# ArduinoMega.net
KiCad netlist of a schematic drawn in Altium Designer
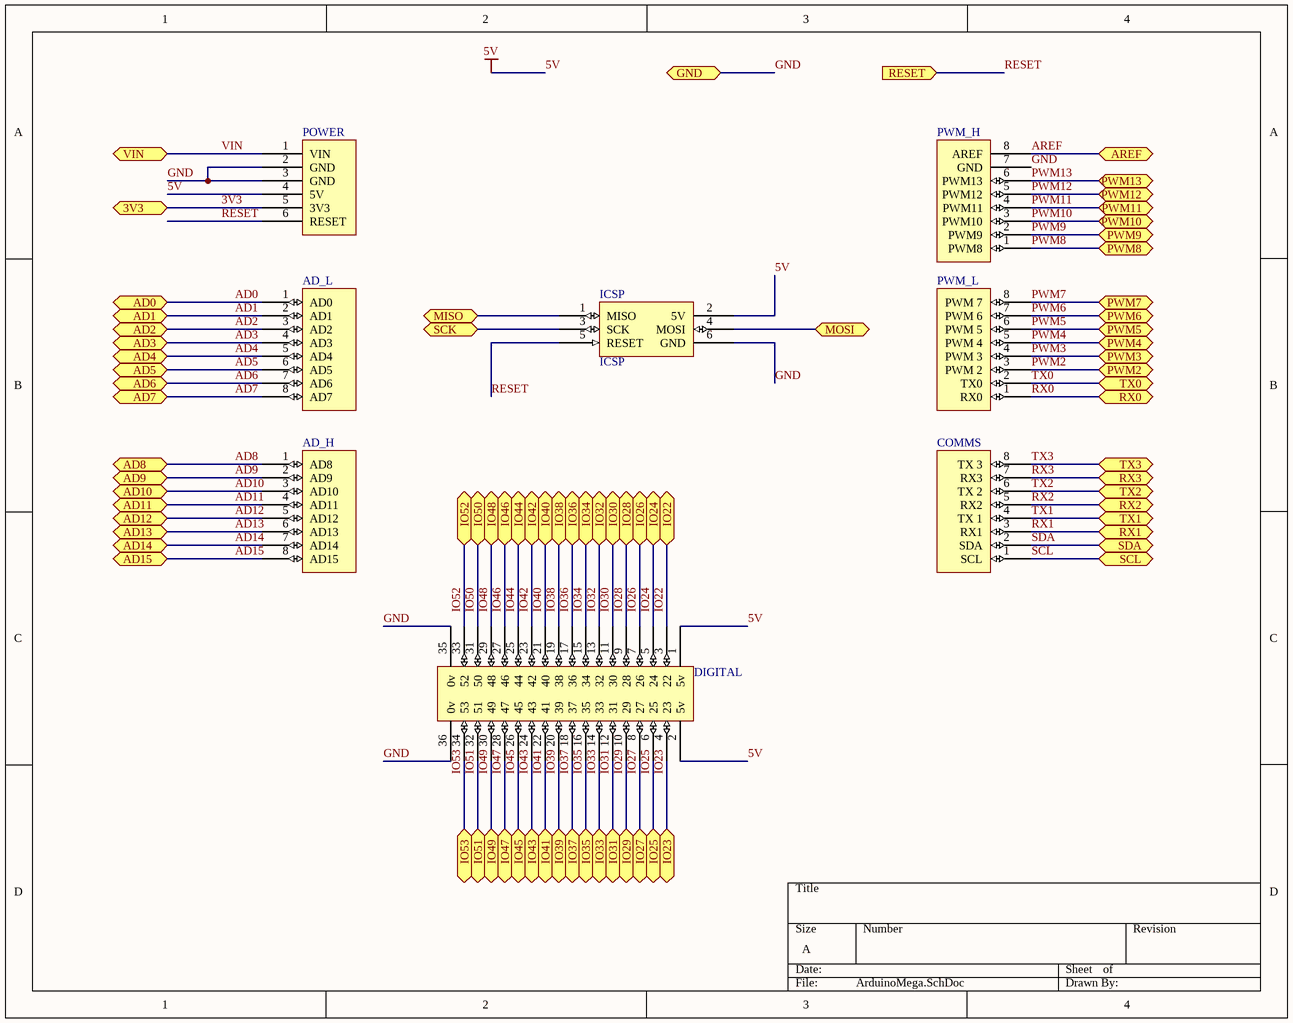
[diagram p0: ArduinoMega.SchDoc]

(export (version "E")
  (design (tool "Eeschema 10.0.6"))
  (components
    (comp (ref "AD_H") (value "AD_H") (footprint "HDR1X8") (libsource (lib "Header") (part "AD_H")))
    (comp (ref "AD_L") (value "AD_L") (footprint "HDR1X8") (libsource (lib "Header") (part "AD_L")))
    (comp (ref "COMMS")
      (value "Communication")
      (footprint "HDR1X8")
      (libsource (lib "Header") (part "Communication"))
    )
    (comp (ref "DIGITAL") (value "IO_36") (footprint "HDR2X18") (libsource (lib "Header") (part "IO_36")))
    (comp (ref "ICSP") (value "ICSP") (footprint "ICSP") (libsource (lib "Header") (part "ICSP")))
    (comp (ref "POWER") (value "POWER") (footprint "HDR1X6") (libsource (lib "Header") (part "POWER")))
    (comp (ref "PWM_H") (value "PWM_H") (footprint "HDR1X8") (libsource (lib "Header") (part "PWM_H")))
    (comp (ref "PWM_L") (value "PWM_L") (footprint "HDR1X8") (libsource (lib "Header") (part "PWM_L")))
  )
  (nets
    (net (code "1") (name "/3V3") (class "Default")
      (node (ref "POWER") (pin "5") (pinfunction "3V3_5") (pintype "power_in"))
    )
    (net (code "2") (name "/AD0") (class "Default")
      (node (ref "AD_L") (pin "1") (pinfunction "AD0_1") (pintype "bidirectional"))
    )
    (net (code "3") (name "/AD1") (class "Default")
      (node (ref "AD_L") (pin "2") (pinfunction "AD1_2") (pintype "bidirectional"))
    )
    (net (code "4") (name "/AD2") (class "Default")
      (node (ref "AD_L") (pin "3") (pinfunction "AD2_3") (pintype "bidirectional"))
    )
    (net (code "5") (name "/AD3") (class "Default")
      (node (ref "AD_L") (pin "4") (pinfunction "AD3_4") (pintype "bidirectional"))
    )
    (net (code "6") (name "/AD4") (class "Default")
      (node (ref "AD_L") (pin "5") (pinfunction "AD4_5") (pintype "bidirectional"))
    )
    (net (code "7") (name "/AD5") (class "Default")
      (node (ref "AD_L") (pin "6") (pinfunction "AD5_6") (pintype "bidirectional"))
    )
    (net (code "8") (name "/AD6") (class "Default")
      (node (ref "AD_L") (pin "7") (pinfunction "AD6_7") (pintype "bidirectional"))
    )
    (net (code "9") (name "/AD7") (class "Default")
      (node (ref "AD_L") (pin "8") (pinfunction "AD7_8") (pintype "bidirectional"))
    )
    (net (code "10") (name "/AD8") (class "Default")
      (node (ref "AD_H") (pin "1") (pinfunction "AD8_1") (pintype "bidirectional"))
    )
    (net (code "11") (name "/AD9") (class "Default")
      (node (ref "AD_H") (pin "2") (pinfunction "AD9_2") (pintype "bidirectional"))
    )
    (net (code "12") (name "/AD10") (class "Default")
      (node (ref "AD_H") (pin "3") (pinfunction "AD10_3") (pintype "bidirectional"))
    )
    (net (code "13") (name "/AD11") (class "Default")
      (node (ref "AD_H") (pin "4") (pinfunction "AD11_4") (pintype "bidirectional"))
    )
    (net (code "14") (name "/AD12") (class "Default")
      (node (ref "AD_H") (pin "5") (pinfunction "AD12_5") (pintype "bidirectional"))
    )
    (net (code "15") (name "/AD13") (class "Default")
      (node (ref "AD_H") (pin "6") (pinfunction "AD13_6") (pintype "bidirectional"))
    )
    (net (code "16") (name "/AD14") (class "Default")
      (node (ref "AD_H") (pin "7") (pinfunction "AD14_7") (pintype "bidirectional"))
    )
    (net (code "17") (name "/AD15") (class "Default")
      (node (ref "AD_H") (pin "8") (pinfunction "AD15_8") (pintype "bidirectional"))
    )
    (net (code "18") (name "/AREF") (class "Default")
      (node (ref "PWM_H") (pin "8") (pinfunction "AREF_8") (pintype "passive"))
    )
    (net (code "19") (name "/GND") (class "Default")
      (node (ref "DIGITAL") (pin "35") (pinfunction "0v_35") (pintype "power_in"))
      (node (ref "DIGITAL") (pin "36") (pinfunction "0v_36") (pintype "power_in"))
      (node (ref "ICSP") (pin "6") (pinfunction "GND_6") (pintype "power_in"))
      (node (ref "POWER") (pin "2") (pinfunction "GND_2") (pintype "power_in"))
      (node (ref "POWER") (pin "3") (pinfunction "GND_3") (pintype "power_in"))
      (node (ref "PWM_H") (pin "7") (pinfunction "GND_7") (pintype "power_in"))
    )
    (net (code "20") (name "/IO22") (class "Default")
      (node (ref "DIGITAL") (pin "3") (pinfunction "22_3") (pintype "bidirectional"))
    )
    (net (code "21") (name "/IO23") (class "Default")
      (node (ref "DIGITAL") (pin "4") (pinfunction "23_4") (pintype "bidirectional"))
    )
    (net (code "22") (name "/IO24") (class "Default")
      (node (ref "DIGITAL") (pin "5") (pinfunction "24_5") (pintype "bidirectional"))
    )
    (net (code "23") (name "/IO25") (class "Default")
      (node (ref "DIGITAL") (pin "6") (pinfunction "25_6") (pintype "bidirectional"))
    )
    (net (code "24") (name "/IO26") (class "Default")
      (node (ref "DIGITAL") (pin "7") (pinfunction "26_7") (pintype "bidirectional"))
    )
    (net (code "25") (name "/IO27") (class "Default")
      (node (ref "DIGITAL") (pin "8") (pinfunction "27_8") (pintype "bidirectional"))
    )
    (net (code "26") (name "/IO28") (class "Default")
      (node (ref "DIGITAL") (pin "9") (pinfunction "28_9") (pintype "bidirectional"))
    )
    (net (code "27") (name "/IO29") (class "Default")
      (node (ref "DIGITAL") (pin "10") (pinfunction "29_10") (pintype "bidirectional"))
    )
    (net (code "28") (name "/IO30") (class "Default")
      (node (ref "DIGITAL") (pin "11") (pinfunction "30_11") (pintype "bidirectional"))
    )
    (net (code "29") (name "/IO31") (class "Default")
      (node (ref "DIGITAL") (pin "12") (pinfunction "31_12") (pintype "bidirectional"))
    )
    (net (code "30") (name "/IO32") (class "Default")
      (node (ref "DIGITAL") (pin "13") (pinfunction "32_13") (pintype "bidirectional"))
    )
    (net (code "31") (name "/IO33") (class "Default")
      (node (ref "DIGITAL") (pin "14") (pinfunction "33_14") (pintype "bidirectional"))
    )
    (net (code "32") (name "/IO34") (class "Default")
      (node (ref "DIGITAL") (pin "15") (pinfunction "34_15") (pintype "bidirectional"))
    )
    (net (code "33") (name "/IO35") (class "Default")
      (node (ref "DIGITAL") (pin "16") (pinfunction "35_16") (pintype "bidirectional"))
    )
    (net (code "34") (name "/IO36") (class "Default")
      (node (ref "DIGITAL") (pin "17") (pinfunction "36_17") (pintype "bidirectional"))
    )
    (net (code "35") (name "/IO37") (class "Default")
      (node (ref "DIGITAL") (pin "18") (pinfunction "37_18") (pintype "bidirectional"))
    )
    (net (code "36") (name "/IO38") (class "Default")
      (node (ref "DIGITAL") (pin "19") (pinfunction "38_19") (pintype "bidirectional"))
    )
    (net (code "37") (name "/IO39") (class "Default")
      (node (ref "DIGITAL") (pin "20") (pinfunction "39_20") (pintype "bidirectional"))
    )
    (net (code "38") (name "/IO40") (class "Default")
      (node (ref "DIGITAL") (pin "21") (pinfunction "40_21") (pintype "bidirectional"))
    )
    (net (code "39") (name "/IO41") (class "Default")
      (node (ref "DIGITAL") (pin "22") (pinfunction "41_22") (pintype "bidirectional"))
    )
    (net (code "40") (name "/IO42") (class "Default")
      (node (ref "DIGITAL") (pin "23") (pinfunction "42_23") (pintype "bidirectional"))
    )
    (net (code "41") (name "/IO43") (class "Default")
      (node (ref "DIGITAL") (pin "24") (pinfunction "43_24") (pintype "bidirectional"))
    )
    (net (code "42") (name "/IO44") (class "Default")
      (node (ref "DIGITAL") (pin "25") (pinfunction "44_25") (pintype "bidirectional"))
    )
    (net (code "43") (name "/IO45") (class "Default")
      (node (ref "DIGITAL") (pin "26") (pinfunction "45_26") (pintype "bidirectional"))
    )
    (net (code "44") (name "/IO46") (class "Default")
      (node (ref "DIGITAL") (pin "27") (pinfunction "46_27") (pintype "bidirectional"))
    )
    (net (code "45") (name "/IO47") (class "Default")
      (node (ref "DIGITAL") (pin "28") (pinfunction "47_28") (pintype "bidirectional"))
    )
    (net (code "46") (name "/IO48") (class "Default")
      (node (ref "DIGITAL") (pin "29") (pinfunction "48_29") (pintype "bidirectional"))
    )
    (net (code "47") (name "/IO49") (class "Default")
      (node (ref "DIGITAL") (pin "30") (pinfunction "49_30") (pintype "bidirectional"))
    )
    (net (code "48") (name "/IO50") (class "Default")
      (node (ref "DIGITAL") (pin "31") (pinfunction "50_31") (pintype "bidirectional"))
    )
    (net (code "49") (name "/IO51") (class "Default")
      (node (ref "DIGITAL") (pin "32") (pinfunction "51_32") (pintype "bidirectional"))
    )
    (net (code "50") (name "/IO52") (class "Default")
      (node (ref "DIGITAL") (pin "33") (pinfunction "52_33") (pintype "bidirectional"))
    )
    (net (code "51") (name "/IO53") (class "Default")
      (node (ref "DIGITAL") (pin "34") (pinfunction "53_34") (pintype "bidirectional"))
    )
    (net (code "52") (name "/MISO") (class "Default")
      (node (ref "ICSP") (pin "1") (pinfunction "MISO_1") (pintype "bidirectional"))
    )
    (net (code "53") (name "/MOSI") (class "Default")
      (node (ref "ICSP") (pin "4") (pinfunction "MOSI_4") (pintype "bidirectional"))
    )
    (net (code "54") (name "/PWM2") (class "Default")
      (node (ref "PWM_L") (pin "3") (pinfunction "PWM_2_3") (pintype "bidirectional"))
    )
    (net (code "55") (name "/PWM3") (class "Default")
      (node (ref "PWM_L") (pin "4") (pinfunction "PWM_3_4") (pintype "bidirectional"))
    )
    (net (code "56") (name "/PWM4") (class "Default")
      (node (ref "PWM_L") (pin "5") (pinfunction "PWM_4_5") (pintype "bidirectional"))
    )
    (net (code "57") (name "/PWM5") (class "Default")
      (node (ref "PWM_L") (pin "6") (pinfunction "PWM_5_6") (pintype "bidirectional"))
    )
    (net (code "58") (name "/PWM6") (class "Default")
      (node (ref "PWM_L") (pin "7") (pinfunction "PWM_6_7") (pintype "bidirectional"))
    )
    (net (code "59") (name "/PWM7") (class "Default")
      (node (ref "PWM_L") (pin "8") (pinfunction "PWM_7_8") (pintype "bidirectional"))
    )
    (net (code "60") (name "/PWM8") (class "Default")
      (node (ref "PWM_H") (pin "1") (pinfunction "PWM8_1") (pintype "bidirectional"))
    )
    (net (code "61") (name "/PWM9") (class "Default")
      (node (ref "PWM_H") (pin "2") (pinfunction "PWM9_2") (pintype "bidirectional"))
    )
    (net (code "62") (name "/PWM10") (class "Default")
      (node (ref "PWM_H") (pin "3") (pinfunction "PWM10_3") (pintype "bidirectional"))
    )
    (net (code "63") (name "/PWM11") (class "Default")
      (node (ref "PWM_H") (pin "4") (pinfunction "PWM11_4") (pintype "bidirectional"))
    )
    (net (code "64") (name "/PWM12") (class "Default")
      (node (ref "PWM_H") (pin "5") (pinfunction "PWM12_5") (pintype "bidirectional"))
    )
    (net (code "65") (name "/PWM13") (class "Default")
      (node (ref "PWM_H") (pin "6") (pinfunction "PWM13_6") (pintype "bidirectional"))
    )
    (net (code "66") (name "/RESET") (class "Default")
      (node (ref "ICSP") (pin "5") (pinfunction "RESET_5") (pintype "input"))
      (node (ref "POWER") (pin "6") (pinfunction "RESET_6") (pintype "passive"))
    )
    (net (code "67") (name "/RX0") (class "Default")
      (node (ref "PWM_L") (pin "1") (pinfunction "RX0_1") (pintype "bidirectional"))
    )
    (net (code "68") (name "/RX1") (class "Default")
      (node (ref "COMMS") (pin "3") (pinfunction "RX1_3") (pintype "bidirectional"))
    )
    (net (code "69") (name "/RX2") (class "Default")
      (node (ref "COMMS") (pin "5") (pinfunction "RX2_5") (pintype "bidirectional"))
    )
    (net (code "70") (name "/RX3") (class "Default")
      (node (ref "COMMS") (pin "7") (pinfunction "RX3_7") (pintype "bidirectional"))
    )
    (net (code "71") (name "/SCK") (class "Default")
      (node (ref "ICSP") (pin "3") (pinfunction "SCK_3") (pintype "bidirectional"))
    )
    (net (code "72") (name "/SCL") (class "Default")
      (node (ref "COMMS") (pin "1") (pinfunction "SCL_1") (pintype "bidirectional"))
    )
    (net (code "73") (name "/SDA") (class "Default")
      (node (ref "COMMS") (pin "2") (pinfunction "SDA_2") (pintype "bidirectional"))
    )
    (net (code "74") (name "/TX0") (class "Default")
      (node (ref "PWM_L") (pin "2") (pinfunction "TX0_2") (pintype "bidirectional"))
    )
    (net (code "75") (name "/TX1") (class "Default")
      (node (ref "COMMS") (pin "4") (pinfunction "TX_1_4") (pintype "bidirectional"))
    )
    (net (code "76") (name "/TX2") (class "Default")
      (node (ref "COMMS") (pin "6") (pinfunction "TX_2_6") (pintype "bidirectional"))
    )
    (net (code "77") (name "/TX3") (class "Default")
      (node (ref "COMMS") (pin "8") (pinfunction "TX_3_8") (pintype "bidirectional"))
    )
    (net (code "78") (name "/VIN") (class "Default")
      (node (ref "POWER") (pin "1") (pinfunction "VIN_1") (pintype "power_in"))
    )
    (net (code "79") (name "5V") (class "Default")
      (node (ref "DIGITAL") (pin "1") (pinfunction "5v_1") (pintype "power_in"))
      (node (ref "DIGITAL") (pin "2") (pinfunction "5v_2") (pintype "power_in"))
      (node (ref "ICSP") (pin "2") (pinfunction "5V_2") (pintype "power_in"))
      (node (ref "POWER") (pin "4") (pinfunction "5V_4") (pintype "power_in"))
    )
  )
)
